# buck_boost_schematic.net
KiCad netlist of a schematic drawn in Altium Designer
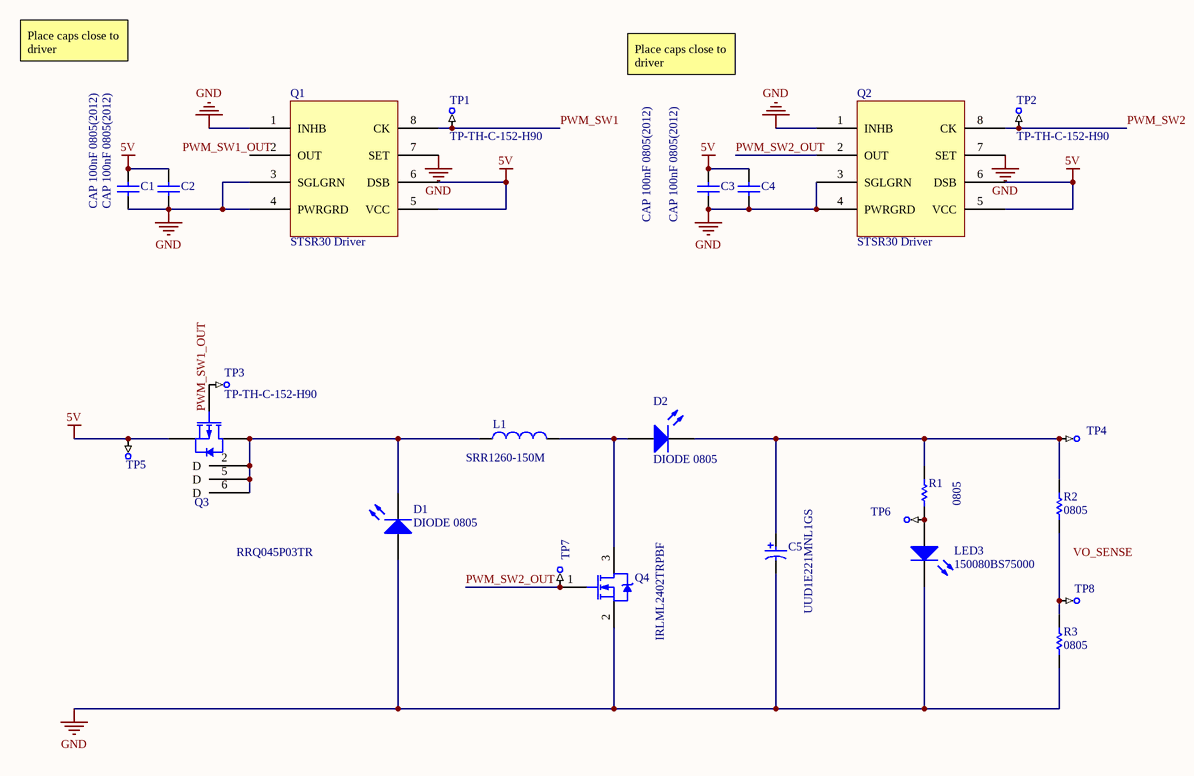
[diagram p0: buck_boost_schematic.SchDoc]

(export (version "E")
  (design (tool "Eeschema 10.0.6"))
  (components
    (comp (ref "C1")
      (value "CAP 100nF 0805(2012)")
      (footprint "CAPC0805(2012)100_L")
      (description "CAP 220nF 6.3V ±10% 0805 (2012 Metric) Thickness 1mm SMD")
      (fields (field (name "TOLERANCE") "Â±10%"))
      (libsource (lib "Altium Content Vault") (part "CMP-1036-04519-1"))
    )
    (comp (ref "C2")
      (value "CAP 100nF 0805(2012)")
      (footprint "CAPC0805(2012)100_L")
      (description "CAP 220nF 6.3V ±10% 0805 (2012 Metric) Thickness 1mm SMD")
      (fields (field (name "TOLERANCE") "Â±10%"))
      (libsource (lib "Altium Content Vault") (part "CMP-1036-04519-1"))
    )
    (comp (ref "C3")
      (value "CAP 100nF 0805(2012)")
      (footprint "CAPC0805(2012)100_L")
      (description "CAP 220nF 6.3V ±10% 0805 (2012 Metric) Thickness 1mm SMD")
      (fields (field (name "TOLERANCE") "Â±10%"))
      (libsource (lib "Altium Content Vault") (part "CMP-1036-04519-1"))
    )
    (comp (ref "C4")
      (value "CAP 100nF 0805(2012)")
      (footprint "CAPC0805(2012)100_L")
      (description "CAP 220nF 6.3V ±10% 0805 (2012 Metric) Thickness 1mm SMD")
      (fields (field (name "TOLERANCE") "Â±10%"))
      (libsource (lib "Altium Content Vault") (part "CMP-1036-04519-1"))
    )
    (comp (ref "C5")
      (value "UUD1E221MNL1GS")
      (footprint "NIC-CAPA2-8X10_V")
      (fields (field (name "MANUFACTURER") "Nichicon"))
      (libsource (lib "Altium Content Vault") (part "NIC-CAP-P-2"))
    )
    (comp (ref "D1")
      (value "DIODE 0805")
      (footprint "0805_A")
      (description "SMD mono-color Chip LED, WL-SMCW, Blue")
      (fields (field (name "MANUFACTURER") "Wuerth Elektronik") (field (name "PARTNUMBER") "150080BS75000"))
      (libsource (lib "Altium Content Vault") (part "WE-LED_K1A2-2"))
    )
    (comp (ref "D2")
      (value "DIODE 0805")
      (footprint "0805_A")
      (description "SMD mono-color Chip LED, WL-SMCW, Blue")
      (fields (field (name "MANUFACTURER") "Wuerth Elektronik") (field (name "PARTNUMBER") "150080BS75000"))
      (libsource (lib "Altium Content Vault") (part "WE-LED_K1A2-2"))
    )
    (comp (ref "L1")
      (value "SRR1260-150M")
      (footprint "BOUR-SRR1260_V")
      (description "Shielded Power Inductor, 15 uH, +/- 20%, -40 to 125 degC, 2-Pin SMD, RoHS, Tape and Reel")
      (fields (field (name "MANUFACTURER") "Bourns") (field (name "TOLERANCE") "20%"))
      (libsource (lib "Altium Content Vault") (part "IND-2"))
    )
    (comp (ref "LED3")
      (value "150080BS75000")
      (footprint "0805_A")
      (description "SMD mono-color Chip LED, WL-SMCW, Blue")
      (fields (field (name "MANUFACTURER") "Wuerth Elektronik"))
      (libsource (lib "Altium Content Vault") (part "WE-LED_K1A2-2"))
    )
    (comp (ref "Q1")
      (value "STSR30 Driver")
      (footprint "NXP-SOT96-1_L")
      (libsource (lib "Schlib1") (part "STSR30"))
    )
    (comp (ref "Q2")
      (value "STSR30 Driver")
      (footprint "NXP-SOT96-1_L")
      (libsource (lib "Schlib1") (part "STSR30"))
    )
    (comp (ref "Q3")
      (value "RRQ045P03TR")
      (footprint "DDC0006A_L")
      (libsource (lib "Schlib1") (part "MOSFET_P - RRQ045P03TR"))
    )
    (comp (ref "Q4")
      (value "IRLML2402TRPBF")
      (footprint "INTR-IRLML2402TRPBF-3_V")
      (description "HEXFET(R) Power MOSFET, N-Channel, 20 V, 1.2 A, 3-Pin SOT-23, RoHS, Tape and Reel")
      (fields (field (name "MANUFACTURER") "International Rectifier"))
      (libsource (lib "Altium Content Vault") (part "NEMOS-GSD-3_A"))
    )
    (comp (ref "R1")
      (value "0805")
      (footprint "RESC0805(2012)_N")
      (description "390R 0.125W 5% 0805 (2012 Metric)  SMD")
      (fields (field (name "POWER") "0.125 W") (field (name "TOLERANCE") "5 %"))
      (libsource (lib "Altium Content Vault") (part "RES"))
    )
    (comp (ref "R2")
      (value "0805")
      (footprint "RESC0805(2012)_N")
      (description "390R 0.125W 5% 0805 (2012 Metric)  SMD")
      (fields (field (name "POWER") "0.125 W") (field (name "TOLERANCE") "5 %"))
      (libsource (lib "Altium Content Vault") (part "RES"))
    )
    (comp (ref "R3")
      (value "0805")
      (footprint "RESC0805(2012)_N")
      (description "390R 0.125W 5% 0805 (2012 Metric)  SMD")
      (fields (field (name "POWER") "0.125 W") (field (name "TOLERANCE") "5 %"))
      (libsource (lib "Altium Content Vault") (part "RES"))
    )
    (comp (ref "TP1")
      (value "TP-TH-C-152-H90")
      (footprint "TP-TH-C-152-H90")
      (description "Test Point, Through Hole, Hole Size 0.9 mm, PCB Mount with Silkscreen Box")
      (fields (field (name "MANUFACTURER") "No Vendor"))
      (libsource (lib "Altium Content Vault") (part "TP-TH"))
    )
    (comp (ref "TP2")
      (value "TP-TH-C-152-H90")
      (footprint "TP-TH-C-152-H90")
      (description "Test Point, Through Hole, Hole Size 0.9 mm, PCB Mount with Silkscreen Box")
      (fields (field (name "MANUFACTURER") "No Vendor"))
      (libsource (lib "Altium Content Vault") (part "TP-TH"))
    )
    (comp (ref "TP3")
      (value "TP-TH-C-152-H90")
      (footprint "TP-TH-C-152-H90")
      (description "Test Point, Through Hole, Hole Size 0.9 mm, PCB Mount with Silkscreen Box")
      (fields (field (name "MANUFACTURER") "No Vendor"))
      (libsource (lib "Altium Content Vault") (part "TP-TH"))
    )
    (comp (ref "TP4")
      (value "~")
      (footprint "TP-TH-C-152-H90")
      (description "Test Point, Through Hole, Hole Size 0.9 mm, PCB Mount with Silkscreen Box")
      (fields (field (name "PARTNUMBER") "TP-TH-C-152-H90") (field (name "MANUFACTURER") "No Vendor"))
      (libsource (lib "Altium Content Vault") (part "TP-TH"))
    )
    (comp (ref "TP5")
      (value "~")
      (footprint "TP-TH-C-152-H90")
      (description "Test Point, Through Hole, Hole Size 0.9 mm, PCB Mount with Silkscreen Box")
      (fields (field (name "PARTNUMBER") "TP-TH-C-152-H90") (field (name "MANUFACTURER") "No Vendor"))
      (libsource (lib "Altium Content Vault") (part "TP-TH"))
    )
    (comp (ref "TP6")
      (value "~")
      (footprint "TP-TH-C-152-H90")
      (description "Test Point, Through Hole, Hole Size 0.9 mm, PCB Mount with Silkscreen Box")
      (fields (field (name "PARTNUMBER") "TP-TH-C-152-H90") (field (name "MANUFACTURER") "No Vendor"))
      (libsource (lib "Altium Content Vault") (part "TP-TH"))
    )
    (comp (ref "TP7")
      (value "~")
      (footprint "TP-TH-C-152-H90")
      (description "Test Point, Through Hole, Hole Size 0.9 mm, PCB Mount with Silkscreen Box")
      (fields (field (name "PARTNUMBER") "TP-TH-C-152-H90") (field (name "MANUFACTURER") "No Vendor"))
      (libsource (lib "Altium Content Vault") (part "TP-TH"))
    )
    (comp (ref "TP8")
      (value "~")
      (footprint "TP-TH-C-152-H90")
      (description "Test Point, Through Hole, Hole Size 0.9 mm, PCB Mount with Silkscreen Box")
      (fields (field (name "PARTNUMBER") "TP-TH-C-152-H90") (field (name "MANUFACTURER") "No Vendor"))
      (libsource (lib "Altium Content Vault") (part "TP-TH"))
    )
  )
  (nets
    (net (code "1") (name "/PWM_SW1") (class "Default")
      (node (ref "Q1") (pin "8") (pinfunction "CK_8") (pintype "passive"))
      (node (ref "TP1") (pin "1") (pinfunction "1_1") (pintype "input"))
    )
    (net (code "3") (name "/PWM_SW2") (class "Default")
      (node (ref "Q2") (pin "8") (pinfunction "CK_8") (pintype "passive"))
      (node (ref "TP2") (pin "1") (pinfunction "1_1") (pintype "input"))
    )
    (net (code "4") (name "/PWM_SW2_OUT") (class "Default")
      (node (ref "Q2") (pin "2") (pinfunction "OUT_2") (pintype "passive"))
      (node (ref "Q4") (pin "1") (pinfunction "G_1") (pintype "passive"))
      (node (ref "TP7") (pin "1") (pinfunction "1_1") (pintype "input"))
    )
    (net (code "6") (name "5V") (class "Default")
      (node (ref "C1") (pin "2") (pinfunction "2_2") (pintype "passive"))
      (node (ref "C2") (pin "2") (pinfunction "2_2") (pintype "passive"))
      (node (ref "C3") (pin "2") (pinfunction "2_2") (pintype "passive"))
      (node (ref "C4") (pin "2") (pinfunction "2_2") (pintype "passive"))
      (node (ref "Q1") (pin "5") (pinfunction "VCC_5") (pintype "passive"))
      (node (ref "Q1") (pin "6") (pinfunction "DSB_6") (pintype "passive"))
      (node (ref "Q2") (pin "5") (pinfunction "VCC_5") (pintype "passive"))
      (node (ref "Q2") (pin "6") (pinfunction "DSB_6") (pintype "passive"))
      (node (ref "Q3") (pin "4") (pinfunction "S_4") (pintype "passive"))
      (node (ref "TP5") (pin "1") (pinfunction "1_1") (pintype "input"))
    )
    (net (code "7") (name "GND") (class "Default")
      (node (ref "C1") (pin "1") (pinfunction "1_1") (pintype "passive"))
      (node (ref "C2") (pin "1") (pinfunction "1_1") (pintype "passive"))
      (node (ref "C3") (pin "1") (pinfunction "1_1") (pintype "passive"))
      (node (ref "C4") (pin "1") (pinfunction "1_1") (pintype "passive"))
      (node (ref "C5") (pin "2") (pinfunction "2_2") (pintype "passive"))
      (node (ref "D1") (pin "2") (pinfunction "A_2") (pintype "passive"))
      (node (ref "LED3") (pin "1") (pinfunction "K_1") (pintype "passive"))
      (node (ref "Q1") (pin "1") (pinfunction "INHB_1") (pintype "passive"))
      (node (ref "Q1") (pin "3") (pinfunction "SGLGRN_3") (pintype "passive"))
      (node (ref "Q1") (pin "4") (pinfunction "PWRGRD_4") (pintype "passive"))
      (node (ref "Q1") (pin "7") (pinfunction "SET_7") (pintype "passive"))
      (node (ref "Q2") (pin "1") (pinfunction "INHB_1") (pintype "passive"))
      (node (ref "Q2") (pin "3") (pinfunction "SGLGRN_3") (pintype "passive"))
      (node (ref "Q2") (pin "4") (pinfunction "PWRGRD_4") (pintype "passive"))
      (node (ref "Q2") (pin "7") (pinfunction "SET_7") (pintype "passive"))
      (node (ref "Q4") (pin "2") (pinfunction "S_2") (pintype "passive"))
      (node (ref "R3") (pin "1") (pinfunction "1_1") (pintype "passive"))
    )
    (net (code "8") (name "Net-(D1-K)") (class "Default")
      (node (ref "D1") (pin "1") (pinfunction "K_1") (pintype "passive"))
      (node (ref "L1") (pin "1") (pinfunction "1_1") (pintype "passive"))
      (node (ref "Q3") (pin "1") (pinfunction "D_1") (pintype "passive"))
      (node (ref "Q3") (pin "2") (pinfunction "D_2") (pintype "passive"))
      (node (ref "Q3") (pin "5") (pinfunction "D_5") (pintype "passive"))
      (node (ref "Q3") (pin "6") (pinfunction "D_6") (pintype "passive"))
    )
    (net (code "9") (name "Net-(D2-A)") (class "Default")
      (node (ref "D2") (pin "2") (pinfunction "A_2") (pintype "passive"))
      (node (ref "L1") (pin "2") (pinfunction "2_2") (pintype "passive"))
      (node (ref "Q4") (pin "3") (pinfunction "D_3") (pintype "passive"))
    )
    (net (code "10") (name "Net-(D2-K)") (class "Default")
      (node (ref "C5") (pin "1") (pinfunction "1_1") (pintype "passive"))
      (node (ref "D2") (pin "1") (pinfunction "K_1") (pintype "passive"))
      (node (ref "R1") (pin "2") (pinfunction "2_2") (pintype "passive"))
      (node (ref "R2") (pin "2") (pinfunction "2_2") (pintype "passive"))
      (node (ref "TP4") (pin "1") (pinfunction "1_1") (pintype "input"))
    )
    (net (code "11") (name "Net-(LED3-A)") (class "Default")
      (node (ref "LED3") (pin "2") (pinfunction "A_2") (pintype "passive"))
      (node (ref "R1") (pin "1") (pinfunction "1_1") (pintype "passive"))
      (node (ref "TP6") (pin "1") (pinfunction "1_1") (pintype "input"))
    )
    (net (code "12") (name "Net-(Q3-G)") (class "Default")
      (node (ref "Q3") (pin "3") (pinfunction "G_3") (pintype "passive"))
      (node (ref "TP3") (pin "1") (pinfunction "1_1") (pintype "input"))
    )
    (net (code "13") (name "Net-(R2-Pad1)") (class "Default")
      (node (ref "R2") (pin "1") (pinfunction "1_1") (pintype "passive"))
      (node (ref "R3") (pin "2") (pinfunction "2_2") (pintype "passive"))
      (node (ref "TP8") (pin "1") (pinfunction "1_1") (pintype "input"))
    )
    (net (code "14") (name "unconnected-(Q1-OUT-Pad2)") (class "Default")
      (node (ref "Q1") (pin "2") (pinfunction "OUT_2") (pintype "passive"))
    )
  )
)
